# gate_driver.net
KiCad netlist of a schematic drawn in Altium Designer
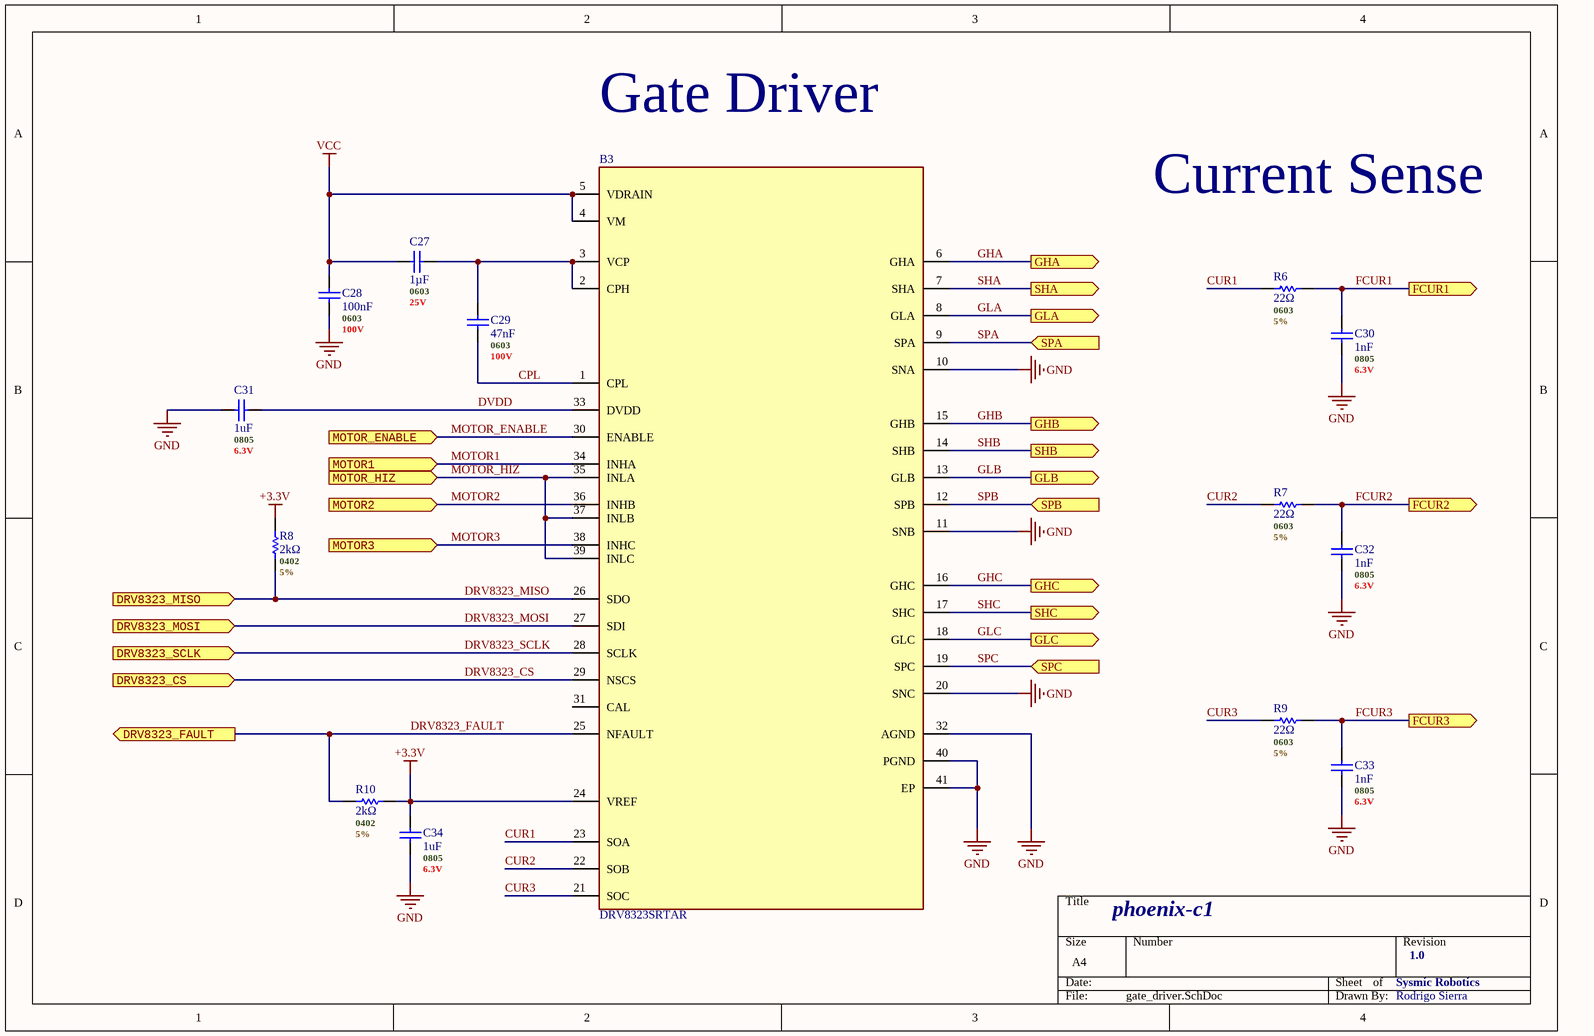
[diagram p0: gate_driver.SchDoc]

(export (version "E")
  (design (tool "Eeschema 10.0.6"))
  (components
    (comp (ref "B3")
      (value "DRV8323SRTAR")
      (footprint "40-WQFN - TEXAS")
      (fields (field (name "MOUSER PART NUMBER") "595-DRV8323SRTAR"))
      (libsource (lib "phoenix-c1-schlib") (part "DRV8323SRTAR"))
    )
    (comp (ref "C27")
      (value "1µF")
      (footprint "C0603 - MURATA")
      (description "25V 1uF X7R 卤10% 0603 Multilayer Ceramic Capacitors MLCC - SMD/SMT ROHS")
      (fields
        (field (name "MANUFACTURER") "TDK")
        (field (name "MANUFACTURER PART NUMBER") "C1608X7R1E105K080AE")
        (field (name ".CASE/PACKAGE") "0603")
        (field (name ".VOLTAGE RATING (DC)") "25V")
      )
      (libsource (lib "CAP - C1608X7R1E105K080AE") (part "C1608X7R1E105K080AE"))
    )
    (comp (ref "C28")
      (value "100nF")
      (footprint "C0603 - MURATA")
      (description "Cap Ceramic 0.1uF 100V X7R 10% Pad SMD 0603 Soft Termination 125C Automotive T/R")
      (fields
        (field (name "MANUFACTURER") "Murata")
        (field (name "MANUFACTURER PART NUMBER") "GCJ188R72A104KA01D")
        (field (name ".CASE/PACKAGE") "0603")
        (field (name ".VOLTAGE RATING (DC)") "100V")
      )
      (libsource (lib "CAP - GCJ188R72A104KA01D") (part "GCJ188R72A104KA01D"))
    )
    (comp (ref "C29")
      (value "47nF")
      (footprint "C0603 - KEMET")
      (description "Multilayer Ceramic Capacitors MLCC - SMD/SMT 100V 0.047uF X7R 0603 10% Flex Soft")
      (fields
        (field (name "MANUFACTURER") "KEMET")
        (field (name "MANUFACTURER PART NUMBER") "C0603X473K1RACTU")
        (field (name ".CASE/PACKAGE") "0603")
        (field (name ".VOLTAGE RATING (DC)") "100V")
      )
      (libsource (lib "CAP - C0603X473K1RACTU") (part "C0603X473K1RACTU"))
    )
    (comp (ref "C30")
      (value "1nF")
      (footprint "C0805 - KYOCERA")
      (description "Multilayer Ceramic Capacitors MLCC - SMD/SMT 6.3V 1000pF X7R 0805 5%")
      (fields
        (field (name "MANUFACTURER") "KYOCERA AVX")
        (field (name "MANUFACTURER PART NUMBER") "08056C102JAT2A")
        (field (name ".CASE/PACKAGE") "0805")
        (field (name ".VOLTAGE RATING (DC)") "6.3V")
      )
      (libsource (lib "CAP - 08056C102JAT2A") (part "08056C102JAT2A"))
    )
    (comp (ref "C31")
      (value "1uF")
      (footprint "C0805 - KYOCERA")
      (description "Multilayer Ceramic Capacitors MLCC - SMD/SMT 6.3V 1uF X7R 0805 20%")
      (fields
        (field (name "MANUFACTURER") "KYOCERA AVX")
        (field (name "MANUFACTURER PART NUMBER") "08056C102JAT2A")
        (field (name ".CASE/PACKAGE") "0805")
        (field (name ".VOLTAGE RATING (DC)") "6.3V")
      )
      (libsource (lib "CAP - 08056C105MAT2A") (part "08056C105MAT2A"))
    )
    (comp (ref "C32")
      (value "1nF")
      (footprint "C0805 - KYOCERA")
      (description "Multilayer Ceramic Capacitors MLCC - SMD/SMT 6.3V 1000pF X7R 0805 5%")
      (fields
        (field (name "MANUFACTURER") "KYOCERA AVX")
        (field (name "MANUFACTURER PART NUMBER") "08056C102JAT2A")
        (field (name ".CASE/PACKAGE") "0805")
        (field (name ".VOLTAGE RATING (DC)") "6.3V")
      )
      (libsource (lib "CAP - 08056C102JAT2A") (part "08056C102JAT2A"))
    )
    (comp (ref "C33")
      (value "1nF")
      (footprint "C0805 - KYOCERA")
      (description "Multilayer Ceramic Capacitors MLCC - SMD/SMT 6.3V 1000pF X7R 0805 5%")
      (fields
        (field (name "MANUFACTURER") "KYOCERA AVX")
        (field (name "MANUFACTURER PART NUMBER") "08056C102JAT2A")
        (field (name ".CASE/PACKAGE") "0805")
        (field (name ".VOLTAGE RATING (DC)") "6.3V")
      )
      (libsource (lib "CAP - 08056C102JAT2A") (part "08056C102JAT2A"))
    )
    (comp (ref "C34")
      (value "1uF")
      (footprint "C0805 - KYOCERA")
      (description "Multilayer Ceramic Capacitors MLCC - SMD/SMT 6.3V 1uF X7R 0805 20%")
      (fields
        (field (name "MANUFACTURER") "KYOCERA AVX")
        (field (name "MANUFACTURER PART NUMBER") "08056C102JAT2A")
        (field (name ".CASE/PACKAGE") "0805")
        (field (name ".VOLTAGE RATING (DC)") "6.3V")
      )
      (libsource (lib "CAP - 08056C105MAT2A") (part "08056C105MAT2A"))
    )
    (comp (ref "R6")
      (value "22Ω")
      (footprint "R0603 - YAGEO")
      (description "100Mw Thick Film Resistors 100Ppm/ 5% 22 0603 Chip Resistor Surface Mount Rohs")
      (fields
        (field (name "MANUFACTURER") "Yageo Group")
        (field (name "MANUFACTURER PART NUMBER") "RC0603JR-0722RL")
        (field (name ".CASE/PACKAGE") "0603")
        (field (name ".TOLERANCE") "5%")
      )
      (libsource (lib "RES - RC0603JR-0722RL") (part "RC0603JR-0722RL"))
    )
    (comp (ref "R7")
      (value "22Ω")
      (footprint "R0603 - YAGEO")
      (description "100Mw Thick Film Resistors 100Ppm/ 5% 22 0603 Chip Resistor Surface Mount Rohs")
      (fields
        (field (name "MANUFACTURER") "Yageo Group")
        (field (name "MANUFACTURER PART NUMBER") "RC0603JR-0722RL")
        (field (name ".CASE/PACKAGE") "0603")
        (field (name ".TOLERANCE") "5%")
      )
      (libsource (lib "RES - RC0603JR-0722RL") (part "RC0603JR-0722RL"))
    )
    (comp (ref "R8")
      (value "2kΩ")
      (footprint "R0402 - YAGEO")
      (description "Anti-Sulfurated Chip Resistor Thick Film 0402 2kOhm 5% Paper T/R")
      (fields
        (field (name "MANUFACTURER") "Yageo Group")
        (field (name "MANUFACTURER PART NUMBER") "AF0402JR-072KL")
        (field (name ".CASE/PACKAGE") "0402")
        (field (name ".TOLERANCE") "5%")
      )
      (libsource (lib "RES - AF024JR-0722KL") (part "AF0402JR-072KL"))
    )
    (comp (ref "R9")
      (value "22Ω")
      (footprint "R0603 - YAGEO")
      (description "100Mw Thick Film Resistors 100Ppm/ 5% 22 0603 Chip Resistor Surface Mount Rohs")
      (fields
        (field (name "MANUFACTURER") "Yageo Group")
        (field (name "MANUFACTURER PART NUMBER") "RC0603JR-0722RL")
        (field (name ".CASE/PACKAGE") "0603")
        (field (name ".TOLERANCE") "5%")
      )
      (libsource (lib "RES - RC0603JR-0722RL") (part "RC0603JR-0722RL"))
    )
    (comp (ref "R10")
      (value "2kΩ")
      (footprint "R0402 - YAGEO")
      (description "Anti-Sulfurated Chip Resistor Thick Film 0402 2kOhm 5% Paper T/R")
      (fields
        (field (name "MANUFACTURER") "Yageo Group")
        (field (name "MANUFACTURER PART NUMBER") "AF0402JR-072KL")
        (field (name ".CASE/PACKAGE") "0402")
        (field (name ".TOLERANCE") "5%")
      )
      (libsource (lib "RES - AF024JR-0722KL") (part "AF0402JR-072KL"))
    )
  )
  (nets
    (net (code "1") (name "+3.3V") (class "Default")
      (node (ref "B3") (pin "24") (pinfunction "VREF_24") (pintype "power_in"))
      (node (ref "C34") (pin "2") (pinfunction "2_2") (pintype "passive"))
      (node (ref "R10") (pin "2") (pinfunction "2_2") (pintype "passive"))
      (node (ref "R8") (pin "1") (pinfunction "1_1") (pintype "passive"))
    )
    (net (code "2") (name "/CPL") (class "Default")
      (node (ref "B3") (pin "1") (pinfunction "CPL_1") (pintype "power_in"))
      (node (ref "C29") (pin "1") (pinfunction "1_1") (pintype "passive"))
    )
    (net (code "3") (name "/CUR1") (class "Default")
      (node (ref "B3") (pin "23") (pinfunction "SOA_23") (pintype "passive"))
      (node (ref "R6") (pin "1") (pinfunction "1_1") (pintype "passive"))
    )
    (net (code "4") (name "/CUR2") (class "Default")
      (node (ref "B3") (pin "22") (pinfunction "SOB_22") (pintype "passive"))
      (node (ref "R7") (pin "1") (pinfunction "1_1") (pintype "passive"))
    )
    (net (code "5") (name "/CUR3") (class "Default")
      (node (ref "B3") (pin "21") (pinfunction "SOC_21") (pintype "passive"))
      (node (ref "R9") (pin "1") (pinfunction "1_1") (pintype "passive"))
    )
    (net (code "6") (name "/DRV8323_CS") (class "Default")
      (node (ref "B3") (pin "29") (pinfunction "NSCS_29") (pintype "passive"))
    )
    (net (code "7") (name "/DRV8323_FAULT") (class "Default")
      (node (ref "B3") (pin "25") (pinfunction "NFAULT_25") (pintype "passive"))
      (node (ref "R10") (pin "1") (pinfunction "1_1") (pintype "passive"))
    )
    (net (code "8") (name "/DRV8323_MISO") (class "Default")
      (node (ref "B3") (pin "26") (pinfunction "SDO_26") (pintype "passive"))
      (node (ref "R8") (pin "2") (pinfunction "2_2") (pintype "passive"))
    )
    (net (code "9") (name "/DRV8323_MOSI") (class "Default")
      (node (ref "B3") (pin "27") (pinfunction "SDI_27") (pintype "passive"))
    )
    (net (code "10") (name "/DRV8323_SCLK") (class "Default")
      (node (ref "B3") (pin "28") (pinfunction "SCLK_28") (pintype "passive"))
    )
    (net (code "11") (name "/DVDD") (class "Default")
      (node (ref "B3") (pin "33") (pinfunction "DVDD_33") (pintype "power_in"))
      (node (ref "C31") (pin "2") (pinfunction "2_2") (pintype "passive"))
    )
    (net (code "12") (name "/FCUR1") (class "Default")
      (node (ref "C30") (pin "2") (pinfunction "2_2") (pintype "passive"))
      (node (ref "R6") (pin "2") (pinfunction "2_2") (pintype "passive"))
    )
    (net (code "13") (name "/FCUR2") (class "Default")
      (node (ref "C32") (pin "2") (pinfunction "2_2") (pintype "passive"))
      (node (ref "R7") (pin "2") (pinfunction "2_2") (pintype "passive"))
    )
    (net (code "14") (name "/FCUR3") (class "Default")
      (node (ref "C33") (pin "2") (pinfunction "2_2") (pintype "passive"))
      (node (ref "R9") (pin "2") (pinfunction "2_2") (pintype "passive"))
    )
    (net (code "15") (name "/GHA") (class "Default")
      (node (ref "B3") (pin "6") (pinfunction "GHA_6") (pintype "passive"))
    )
    (net (code "16") (name "/GHB") (class "Default")
      (node (ref "B3") (pin "15") (pinfunction "GHB_15") (pintype "passive"))
    )
    (net (code "17") (name "/GHC") (class "Default")
      (node (ref "B3") (pin "16") (pinfunction "GHC_16") (pintype "passive"))
    )
    (net (code "18") (name "/GLA") (class "Default")
      (node (ref "B3") (pin "8") (pinfunction "GLA_8") (pintype "passive"))
    )
    (net (code "19") (name "/GLB") (class "Default")
      (node (ref "B3") (pin "13") (pinfunction "GLB_13") (pintype "passive"))
    )
    (net (code "20") (name "/GLC") (class "Default")
      (node (ref "B3") (pin "18") (pinfunction "GLC_18") (pintype "passive"))
    )
    (net (code "21") (name "/MOTOR1") (class "Default")
      (node (ref "B3") (pin "34") (pinfunction "INHA_34") (pintype "passive"))
    )
    (net (code "22") (name "/MOTOR2") (class "Default")
      (node (ref "B3") (pin "36") (pinfunction "INHB_36") (pintype "passive"))
    )
    (net (code "23") (name "/MOTOR3") (class "Default")
      (node (ref "B3") (pin "38") (pinfunction "INHC_38") (pintype "passive"))
    )
    (net (code "24") (name "/MOTOR_ENABLE") (class "Default")
      (node (ref "B3") (pin "30") (pinfunction "ENABLE_30") (pintype "passive"))
    )
    (net (code "25") (name "/MOTOR_HIZ") (class "Default")
      (node (ref "B3") (pin "35") (pinfunction "INLA_35") (pintype "passive"))
      (node (ref "B3") (pin "37") (pinfunction "INLB_37") (pintype "passive"))
      (node (ref "B3") (pin "39") (pinfunction "INLC_39") (pintype "passive"))
    )
    (net (code "26") (name "/SHA") (class "Default")
      (node (ref "B3") (pin "7") (pinfunction "SHA_7") (pintype "passive"))
    )
    (net (code "27") (name "/SHB") (class "Default")
      (node (ref "B3") (pin "14") (pinfunction "SHB_14") (pintype "passive"))
    )
    (net (code "28") (name "/SHC") (class "Default")
      (node (ref "B3") (pin "17") (pinfunction "SHC_17") (pintype "passive"))
    )
    (net (code "29") (name "/SPA") (class "Default")
      (node (ref "B3") (pin "9") (pinfunction "SPA_9") (pintype "passive"))
    )
    (net (code "30") (name "/SPB") (class "Default")
      (node (ref "B3") (pin "12") (pinfunction "SPB_12") (pintype "passive"))
    )
    (net (code "31") (name "/SPC") (class "Default")
      (node (ref "B3") (pin "19") (pinfunction "SPC_19") (pintype "passive"))
    )
    (net (code "32") (name "GND") (class "Default")
      (node (ref "B3") (pin "10") (pinfunction "SNA_10") (pintype "passive"))
      (node (ref "B3") (pin "11") (pinfunction "SNB_11") (pintype "passive"))
      (node (ref "B3") (pin "20") (pinfunction "SNC_20") (pintype "passive"))
      (node (ref "B3") (pin "32") (pinfunction "AGND_32") (pintype "power_in"))
      (node (ref "B3") (pin "40") (pinfunction "PGND_40") (pintype "power_in"))
      (node (ref "B3") (pin "41") (pinfunction "EP_41") (pintype "passive"))
      (node (ref "C28") (pin "1") (pinfunction "1_1") (pintype "passive"))
      (node (ref "C30") (pin "1") (pinfunction "1_1") (pintype "passive"))
      (node (ref "C31") (pin "1") (pinfunction "1_1") (pintype "passive"))
      (node (ref "C32") (pin "1") (pinfunction "1_1") (pintype "passive"))
      (node (ref "C33") (pin "1") (pinfunction "1_1") (pintype "passive"))
      (node (ref "C34") (pin "1") (pinfunction "1_1") (pintype "passive"))
    )
    (net (code "33") (name "Net-(B3-CPH)") (class "Default")
      (node (ref "B3") (pin "2") (pinfunction "CPH_2") (pintype "power_in"))
      (node (ref "B3") (pin "3") (pinfunction "VCP_3") (pintype "power_in"))
      (node (ref "C27") (pin "2") (pinfunction "2_2") (pintype "passive"))
      (node (ref "C29") (pin "2") (pinfunction "2_2") (pintype "passive"))
    )
    (net (code "34") (name "VCC") (class "Default")
      (node (ref "B3") (pin "4") (pinfunction "VM_4") (pintype "power_in"))
      (node (ref "B3") (pin "5") (pinfunction "VDRAIN_5") (pintype "passive"))
      (node (ref "C27") (pin "1") (pinfunction "1_1") (pintype "passive"))
      (node (ref "C28") (pin "2") (pinfunction "2_2") (pintype "passive"))
    )
    (net (code "35") (name "unconnected-(B3-CAL-Pad31)") (class "Default")
      (node (ref "B3") (pin "31") (pinfunction "CAL_31") (pintype "passive"))
    )
  )
)
